# SD_Smart_Card.net
KiCad netlist of a schematic drawn in Altium Designer
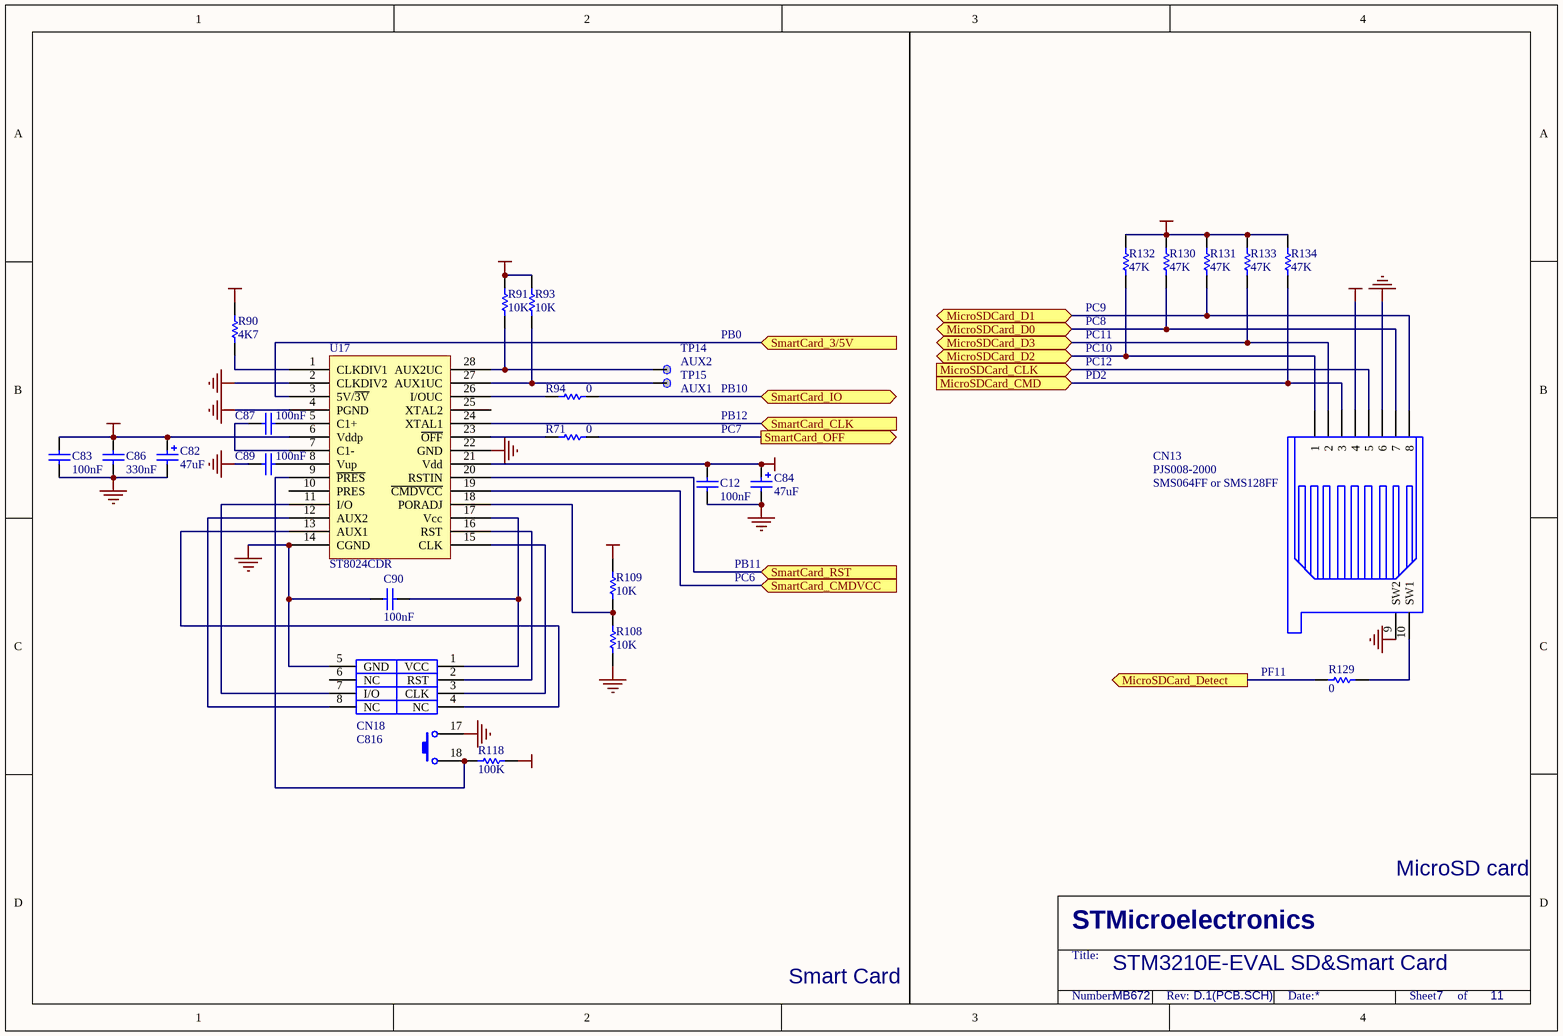
[diagram p0: SD&Smart Card.SchDoc]

(export (version "E")
  (design (tool "Eeschema 10.0.6"))
  (components
    (comp (ref "C12")
      (value "100nF")
      (footprint "0603P")
      (description "Capacitor")
      (fields (field (name "PUBLISHER") "Altium Limited"))
      (libsource (lib "Miscellaneous Devices") (part "CAP"))
    )
    (comp (ref "C82")
      (value "47uF")
      (footprint "TAN-B")
      (description "Polarized Capacitor (Radial)")
      (fields (field (name "PUBLISHER") "Altium Limited"))
      (libsource (lib "Miscellaneous Devices") (part "Cap Pol1"))
    )
    (comp (ref "C83")
      (value "100nF")
      (footprint "0603P")
      (description "Capacitor")
      (fields (field (name "PUBLISHER") "Altium Limited"))
      (libsource (lib "Miscellaneous Devices") (part "CAP"))
    )
    (comp (ref "C84")
      (value "47uF")
      (footprint "TAN-B")
      (description "Polarized Capacitor (Radial)")
      (fields (field (name "PUBLISHER") "Altium Limited"))
      (libsource (lib "Miscellaneous Devices") (part "Cap Pol1"))
    )
    (comp (ref "C86")
      (value "330nF")
      (description "Capacitor")
      (fields (field (name "PUBLISHER") "Altium Limited"))
      (libsource (lib "Miscellaneous Devices") (part "CAP"))
    )
    (comp (ref "C87")
      (value "100nF")
      (footprint "0603P")
      (description "Capacitor")
      (fields (field (name "PUBLISHER") "Altium Limited"))
      (libsource (lib "Miscellaneous Devices") (part "CAP"))
    )
    (comp (ref "C89")
      (value "100nF")
      (footprint "0603P")
      (description "Capacitor")
      (fields (field (name "PUBLISHER") "Altium Limited"))
      (libsource (lib "Miscellaneous Devices") (part "CAP"))
    )
    (comp (ref "C90")
      (value "100nF")
      (footprint "0603P")
      (description "Capacitor")
      (fields (field (name "PUBLISHER") "Altium Limited"))
      (libsource (lib "Miscellaneous Devices") (part "CAP"))
    )
    (comp (ref "CN13")
      (value "PJS008-2000")
      (footprint "MSD(PJS008)")
      (libsource (lib "MB525") (part "SMS016AFA5E"))
    )
    (comp (ref "CN18")
      (value "C816")
      (footprint "SAM(C816)")
      (libsource (lib "MB525") (part "Smart_card_CN"))
    )
    (comp (ref "R71")
      (value "0")
      (description "Resistor")
      (fields (field (name "PUBLISHER") "Altium Limited"))
      (libsource (lib "Miscellaneous Devices") (part "Res1"))
    )
    (comp (ref "R90")
      (value "4K7")
      (description "Resistor")
      (fields (field (name "PUBLISHER") "Altium Limited"))
      (libsource (lib "Miscellaneous Devices") (part "Res1"))
    )
    (comp (ref "R91")
      (value "10K")
      (description "Resistor")
      (fields (field (name "PUBLISHER") "Altium Limited"))
      (libsource (lib "Miscellaneous Devices") (part "Res1"))
    )
    (comp (ref "R93")
      (value "10K")
      (description "Resistor")
      (fields (field (name "PUBLISHER") "Altium Limited"))
      (libsource (lib "Miscellaneous Devices") (part "Res1"))
    )
    (comp (ref "R94")
      (value "0")
      (description "Resistor")
      (fields (field (name "PUBLISHER") "Altium Limited"))
      (libsource (lib "Miscellaneous Devices") (part "Res1"))
    )
    (comp (ref "R108")
      (value "10K")
      (description "Resistor")
      (fields (field (name "PUBLISHER") "Altium Limited"))
      (libsource (lib "Miscellaneous Devices") (part "Res1"))
    )
    (comp (ref "R109")
      (value "10K")
      (description "Resistor")
      (fields (field (name "PUBLISHER") "Altium Limited"))
      (libsource (lib "Miscellaneous Devices") (part "Res1"))
    )
    (comp (ref "R118")
      (value "100K")
      (description "Resistor")
      (fields (field (name "PUBLISHER") "Altium Limited"))
      (libsource (lib "Miscellaneous Devices") (part "Res1"))
    )
    (comp (ref "R129")
      (value "0")
      (description "Resistor")
      (fields (field (name "PUBLISHER") "Altium Limited"))
      (libsource (lib "Miscellaneous Devices") (part "Res1"))
    )
    (comp (ref "R130")
      (value "47K")
      (description "Resistor")
      (fields (field (name "PUBLISHER") "Altium Limited"))
      (libsource (lib "Miscellaneous Devices") (part "Res1"))
    )
    (comp (ref "R131")
      (value "47K")
      (description "Resistor")
      (fields (field (name "PUBLISHER") "Altium Limited"))
      (libsource (lib "Miscellaneous Devices") (part "Res1"))
    )
    (comp (ref "R132")
      (value "47K")
      (description "Resistor")
      (fields (field (name "PUBLISHER") "Altium Limited"))
      (libsource (lib "Miscellaneous Devices") (part "Res1"))
    )
    (comp (ref "R133")
      (value "47K")
      (description "Resistor")
      (fields (field (name "PUBLISHER") "Altium Limited"))
      (libsource (lib "Miscellaneous Devices") (part "Res1"))
    )
    (comp (ref "R134")
      (value "47K")
      (description "Resistor")
      (fields (field (name "PUBLISHER") "Altium Limited"))
      (libsource (lib "Miscellaneous Devices") (part "Res1"))
    )
    (comp (ref "TP14") (value "AUX2") (footprint "TP") (libsource (lib "*") (part "TP")))
    (comp (ref "TP15") (value "AUX1") (footprint "TP") (libsource (lib "*") (part "TP")))
    (comp (ref "U17") (value "ST8024CDR") (footprint "SO28") (libsource (lib "MB525") (part "ST8024CTR")))
  )
  (nets
    (net (code "1") (name "+3V3") (class "Default")
      (node (ref "C12") (pin "1") (pinfunction "1_1") (pintype "passive"))
      (node (ref "C84") (pin "1") (pinfunction "1_1") (pintype "passive"))
      (node (ref "CN13") (pin "4") (pinfunction "4_4") (pintype "passive"))
      (node (ref "R109") (pin "1") (pinfunction "1_1") (pintype "passive"))
      (node (ref "R118") (pin "1") (pinfunction "1_1") (pintype "passive"))
      (node (ref "R130") (pin "1") (pinfunction "1_1") (pintype "passive"))
      (node (ref "R131") (pin "1") (pinfunction "1_1") (pintype "passive"))
      (node (ref "R132") (pin "1") (pinfunction "1_1") (pintype "passive"))
      (node (ref "R133") (pin "1") (pinfunction "1_1") (pintype "passive"))
      (node (ref "R134") (pin "1") (pinfunction "1_1") (pintype "passive"))
      (node (ref "R90") (pin "1") (pinfunction "1_1") (pintype "passive"))
      (node (ref "R91") (pin "1") (pinfunction "1_1") (pintype "passive"))
      (node (ref "R93") (pin "1") (pinfunction "1_1") (pintype "passive"))
      (node (ref "U17") (pin "21") (pinfunction "Vdd_21") (pintype "passive"))
    )
    (net (code "2") (name "+5V") (class "Default")
      (node (ref "C82") (pin "1") (pinfunction "1_1") (pintype "passive"))
      (node (ref "C83") (pin "1") (pinfunction "1_1") (pintype "passive"))
      (node (ref "C86") (pin "1") (pinfunction "1_1") (pintype "passive"))
      (node (ref "U17") (pin "6") (pinfunction "Vddp_6") (pintype "passive"))
    )
    (net (code "3") (name "/MicroSDCard_CLK") (class "Default")
      (node (ref "CN13") (pin "5") (pinfunction "5_5") (pintype "passive"))
    )
    (net (code "4") (name "/MicroSDCard_CMD") (class "Default")
      (node (ref "CN13") (pin "3") (pinfunction "3_3") (pintype "passive"))
      (node (ref "R134") (pin "2") (pinfunction "2_2") (pintype "passive"))
    )
    (net (code "5") (name "/MicroSDCard_D0") (class "Default")
      (node (ref "CN13") (pin "7") (pinfunction "7_7") (pintype "passive"))
      (node (ref "R130") (pin "2") (pinfunction "2_2") (pintype "passive"))
    )
    (net (code "6") (name "/MicroSDCard_D1") (class "Default")
      (node (ref "CN13") (pin "8") (pinfunction "8_8") (pintype "passive"))
      (node (ref "R131") (pin "2") (pinfunction "2_2") (pintype "passive"))
    )
    (net (code "7") (name "/MicroSDCard_D2") (class "Default")
      (node (ref "CN13") (pin "1") (pinfunction "1_1") (pintype "passive"))
      (node (ref "R132") (pin "2") (pinfunction "2_2") (pintype "passive"))
    )
    (net (code "8") (name "/MicroSDCard_D3") (class "Default")
      (node (ref "CN13") (pin "2") (pinfunction "2_2") (pintype "passive"))
      (node (ref "R133") (pin "2") (pinfunction "2_2") (pintype "passive"))
    )
    (net (code "9") (name "/MicroSDCard_Detect") (class "Default")
      (node (ref "R129") (pin "1") (pinfunction "1_1") (pintype "passive"))
    )
    (net (code "10") (name "/SmartCard_3{slash}5V") (class "Default")
      (node (ref "U17") (pin "3") (pinfunction "5V/~{3V}_3") (pintype "passive"))
    )
    (net (code "11") (name "/SmartCard_CLK") (class "Default")
      (node (ref "U17") (pin "24") (pinfunction "XTAL1_24") (pintype "passive"))
    )
    (net (code "12") (name "/SmartCard_CMDVCC") (class "Default")
      (node (ref "U17") (pin "19") (pinfunction "~{CMDVCC}_19") (pintype "passive"))
    )
    (net (code "13") (name "/SmartCard_IO") (class "Default")
      (node (ref "R94") (pin "2") (pinfunction "2_2") (pintype "passive"))
    )
    (net (code "14") (name "/SmartCard_OFF") (class "Default")
      (node (ref "R71") (pin "1") (pinfunction "1_1") (pintype "passive"))
    )
    (net (code "15") (name "/SmartCard_RST") (class "Default")
      (node (ref "U17") (pin "20") (pinfunction "RSTIN_20") (pintype "passive"))
    )
    (net (code "16") (name "GND") (class "Default")
      (node (ref "C12") (pin "2") (pinfunction "2_2") (pintype "passive"))
      (node (ref "C82") (pin "2") (pinfunction "2_2") (pintype "passive"))
      (node (ref "C83") (pin "2") (pinfunction "2_2") (pintype "passive"))
      (node (ref "C84") (pin "2") (pinfunction "2_2") (pintype "passive"))
      (node (ref "C86") (pin "2") (pinfunction "2_2") (pintype "passive"))
      (node (ref "C89") (pin "2") (pinfunction "2_2") (pintype "passive"))
      (node (ref "C90") (pin "1") (pinfunction "1_1") (pintype "passive"))
      (node (ref "CN13") (pin "6") (pinfunction "6_6") (pintype "passive"))
      (node (ref "CN13") (pin "9") (pinfunction "SW2_9") (pintype "passive"))
      (node (ref "CN18") (pin "17") (pintype "passive"))
      (node (ref "CN18") (pin "5") (pinfunction "GND_5") (pintype "passive"))
      (node (ref "R108") (pin "2") (pinfunction "2_2") (pintype "passive"))
      (node (ref "U17") (pin "14") (pinfunction "CGND_14") (pintype "passive"))
      (node (ref "U17") (pin "2") (pinfunction "CLKDIV2_2") (pintype "passive"))
      (node (ref "U17") (pin "22") (pinfunction "GND_22") (pintype "passive"))
      (node (ref "U17") (pin "4") (pinfunction "PGND_4") (pintype "passive"))
    )
    (net (code "17") (name "Net-(CN13-SW1)") (class "Default")
      (node (ref "CN13") (pin "10") (pinfunction "SW1_10") (pintype "passive"))
      (node (ref "R129") (pin "2") (pinfunction "2_2") (pintype "passive"))
    )
    (net (code "18") (name "Net-(CN18-CLK)") (class "Default")
      (node (ref "CN18") (pin "3") (pinfunction "CLK_3") (pintype "passive"))
      (node (ref "U17") (pin "15") (pinfunction "CLK_15") (pintype "passive"))
    )
    (net (code "19") (name "Net-(CN18-I{slash}O)") (class "Default")
      (node (ref "CN18") (pin "7") (pinfunction "I/O_7") (pintype "passive"))
      (node (ref "U17") (pin "11") (pinfunction "I/O_11") (pintype "passive"))
    )
    (net (code "20") (name "Net-(CN18-RST)") (class "Default")
      (node (ref "CN18") (pin "2") (pinfunction "RST_2") (pintype "passive"))
      (node (ref "U17") (pin "16") (pinfunction "RST_16") (pintype "passive"))
    )
    (net (code "21") (name "Net-(CN18-VCC)") (class "Default")
      (node (ref "C90") (pin "2") (pinfunction "2_2") (pintype "passive"))
      (node (ref "CN18") (pin "1") (pinfunction "VCC_1") (pintype "passive"))
      (node (ref "U17") (pin "17") (pinfunction "Vcc_17") (pintype "passive"))
    )
    (net (code "22") (name "Net-(U17-AUX1)") (class "Default")
      (node (ref "CN18") (pin "4") (pinfunction "NC_4") (pintype "passive"))
      (node (ref "U17") (pin "13") (pinfunction "AUX1_13") (pintype "passive"))
    )
    (net (code "23") (name "Net-(U17-AUX1UC)") (class "Default")
      (node (ref "R93") (pin "2") (pinfunction "2_2") (pintype "passive"))
      (node (ref "TP15") (pin "1") (pinfunction "1_1") (pintype "passive"))
      (node (ref "U17") (pin "27") (pinfunction "AUX1UC_27") (pintype "passive"))
    )
    (net (code "24") (name "Net-(U17-AUX2)") (class "Default")
      (node (ref "CN18") (pin "8") (pinfunction "NC_8") (pintype "passive"))
      (node (ref "U17") (pin "12") (pinfunction "AUX2_12") (pintype "passive"))
    )
    (net (code "25") (name "Net-(U17-AUX2UC)") (class "Default")
      (node (ref "R91") (pin "2") (pinfunction "2_2") (pintype "passive"))
      (node (ref "TP14") (pin "1") (pinfunction "1_1") (pintype "passive"))
      (node (ref "U17") (pin "28") (pinfunction "AUX2UC_28") (pintype "passive"))
    )
    (net (code "26") (name "Net-(U17-C1+)") (class "Default")
      (node (ref "C87") (pin "2") (pinfunction "2_2") (pintype "passive"))
      (node (ref "U17") (pin "5") (pinfunction "C1+_5") (pintype "passive"))
    )
    (net (code "27") (name "Net-(U17-C1-)") (class "Default")
      (node (ref "C87") (pin "1") (pinfunction "1_1") (pintype "passive"))
      (node (ref "U17") (pin "7") (pinfunction "C1-_7") (pintype "passive"))
    )
    (net (code "28") (name "Net-(U17-CLKDIV1)") (class "Default")
      (node (ref "R90") (pin "2") (pinfunction "2_2") (pintype "passive"))
      (node (ref "U17") (pin "1") (pinfunction "CLKDIV1_1") (pintype "passive"))
    )
    (net (code "29") (name "Net-(U17-I{slash}OUC)") (class "Default")
      (node (ref "R94") (pin "1") (pinfunction "1_1") (pintype "passive"))
      (node (ref "U17") (pin "26") (pinfunction "I/OUC_26") (pintype "passive"))
    )
    (net (code "30") (name "Net-(U17-PORADJ)") (class "Default")
      (node (ref "R108") (pin "1") (pinfunction "1_1") (pintype "passive"))
      (node (ref "R109") (pin "2") (pinfunction "2_2") (pintype "passive"))
      (node (ref "U17") (pin "18") (pinfunction "PORADJ_18") (pintype "passive"))
    )
    (net (code "31") (name "Net-(U17-Vup)") (class "Default")
      (node (ref "C89") (pin "1") (pinfunction "1_1") (pintype "passive"))
      (node (ref "U17") (pin "8") (pinfunction "Vup_8") (pintype "passive"))
    )
    (net (code "32") (name "Net-(U17-~{OFF})") (class "Default")
      (node (ref "R71") (pin "2") (pinfunction "2_2") (pintype "passive"))
      (node (ref "U17") (pin "23") (pinfunction "~{OFF}_23") (pintype "passive"))
    )
    (net (code "33") (name "Net-(U17-~{PRES})") (class "Default")
      (node (ref "CN18") (pin "18") (pintype "passive"))
      (node (ref "R118") (pin "2") (pinfunction "2_2") (pintype "passive"))
      (node (ref "U17") (pin "9") (pinfunction "~{PRES}_9") (pintype "passive"))
    )
    (net (code "34") (name "unconnected-(CN18-NC-Pad6)") (class "Default")
      (node (ref "CN18") (pin "6") (pinfunction "NC_6") (pintype "passive"))
    )
    (net (code "35") (name "unconnected-(U17-PRES-Pad10)") (class "Default")
      (node (ref "U17") (pin "10") (pinfunction "PRES_10") (pintype "passive"))
    )
    (net (code "36") (name "unconnected-(U17-XTAL2-Pad25)") (class "Default")
      (node (ref "U17") (pin "25") (pinfunction "XTAL2_25") (pintype "passive"))
    )
  )
)
